# Nu_Preamp.net
KiCad netlist of a schematic drawn in EAGLE
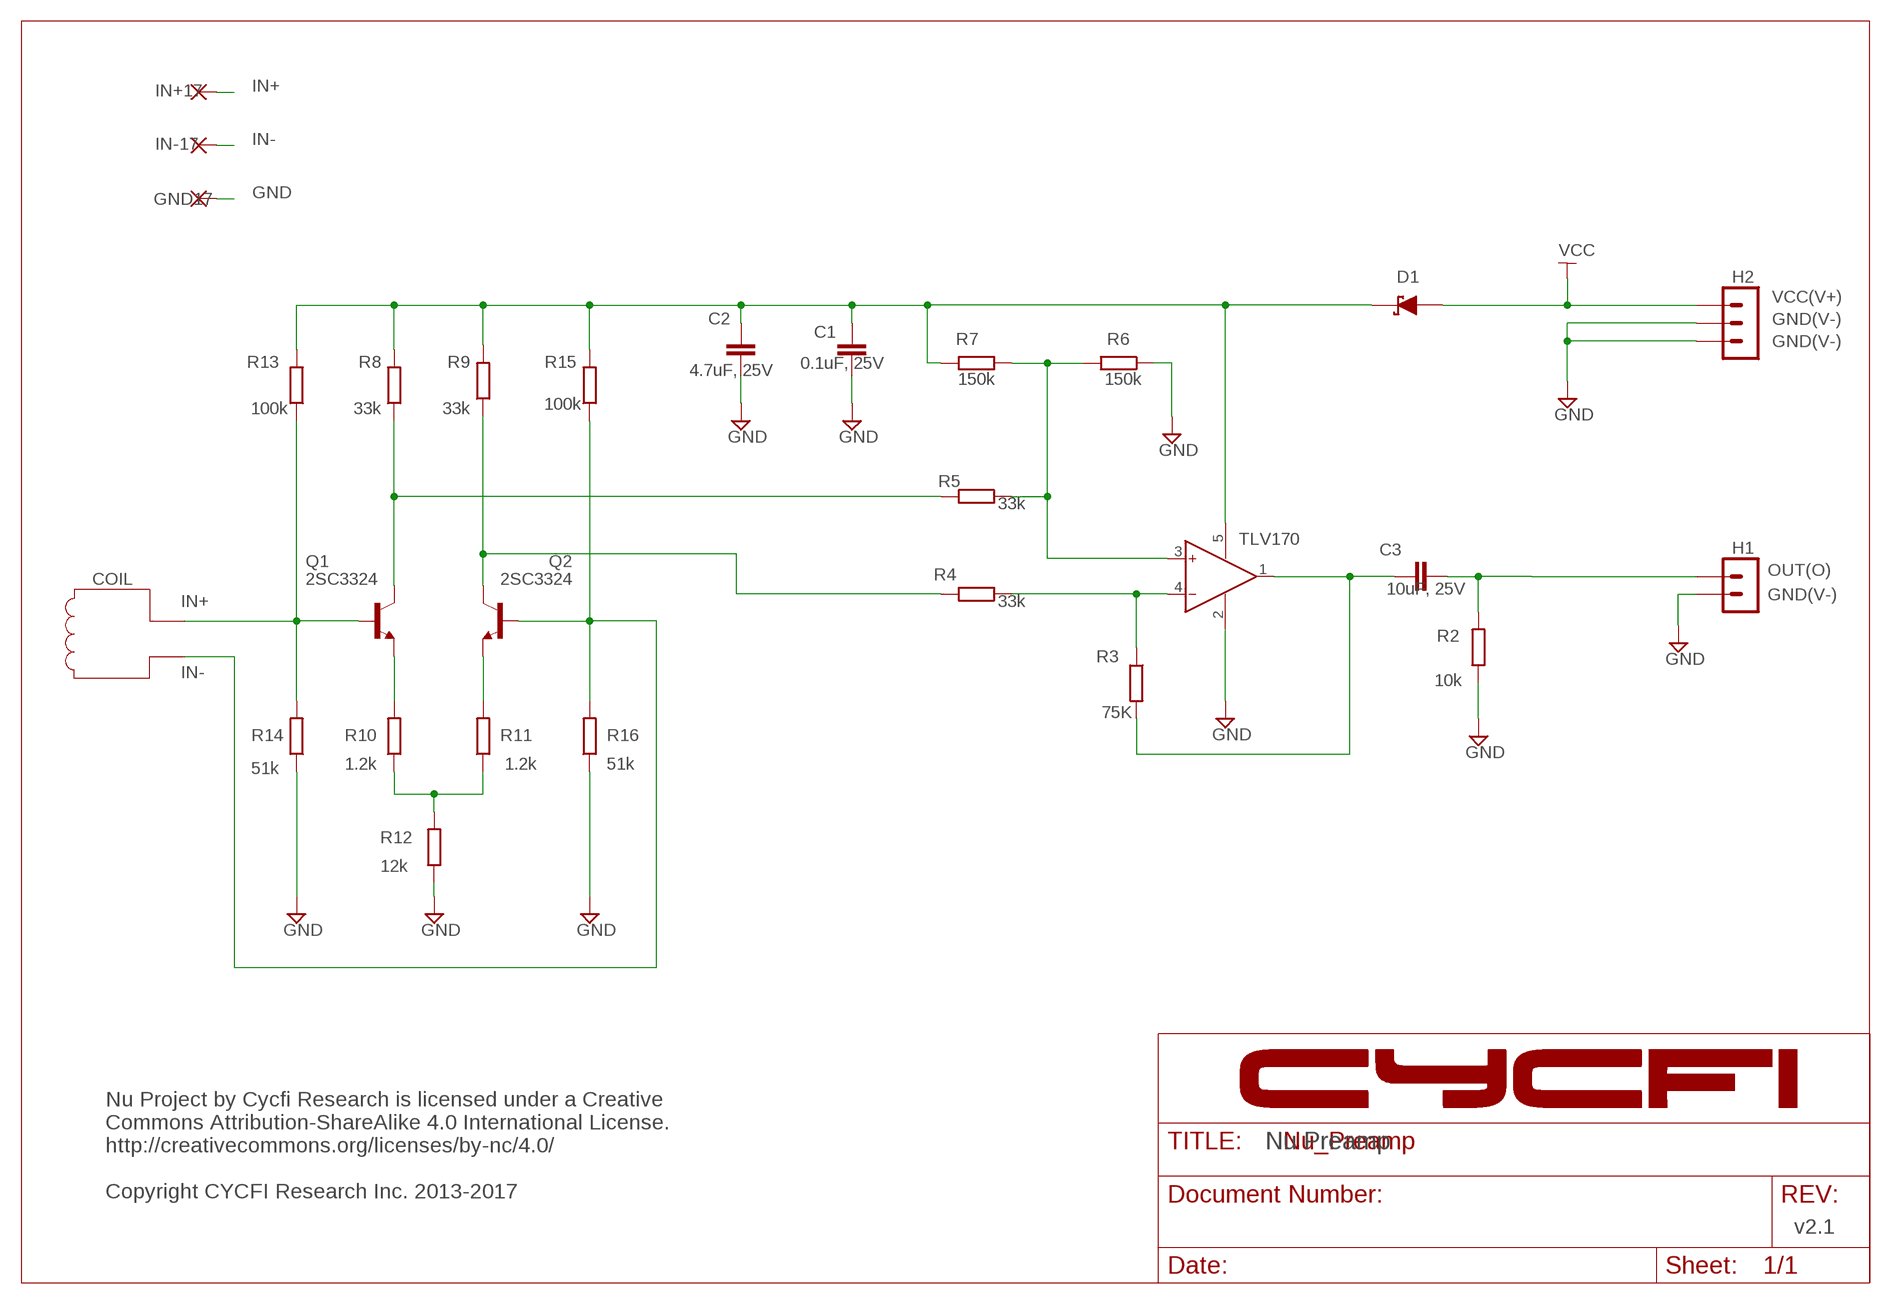
[diagram p0: schematic, sheet 1]

(export (version "E")
  (design (tool "Eeschema 10.0.6"))
  (components
    (comp (ref "C1")
      (value "0.1uF, 25V")
      (footprint "eagle-import:C0402")
      (libsource (lib "eagle-import") (part "C-EUC0402"))
    )
    (comp (ref "C2")
      (value "4.7uF, 25V")
      (footprint "eagle-import:C0603_NK")
      (libsource (lib "eagle-import") (part "C0603_NK"))
    )
    (comp (ref "C3")
      (value "10uF, 25V")
      (footprint "eagle-import:C0603_NK")
      (libsource (lib "eagle-import") (part "C0603_NK"))
    )
    (comp (ref "D1")
      (value "D-SCHOTKKY_SOD323")
      (footprint "eagle-import:SOD323")
      (libsource (lib "eagle-import") (part "D-SCHOTKKY_SOD323"))
    )
    (comp (ref "GND17")
      (value "SMD2")
      (footprint "eagle-import:SMD1,27-2,54")
      (libsource (lib "eagle-import") (part "SMD2"))
    )
    (comp (ref "H1")
      (value "2P-2MM-TH-MALE")
      (footprint "eagle-import:2P-2MM-TH")
      (libsource (lib "eagle-import") (part "2P-2MM-TH-MALE"))
    )
    (comp (ref "H2")
      (value "3P-2MM-TH-MALE")
      (footprint "eagle-import:3P-2MM-TH")
      (libsource (lib "eagle-import") (part "3P-2MM-TH-MALE"))
    )
    (comp (ref "IN+17")
      (value "SMD2")
      (footprint "eagle-import:SMD1,27-2,54")
      (libsource (lib "eagle-import") (part "SMD2"))
    )
    (comp (ref "IN-17")
      (value "SMD2")
      (footprint "eagle-import:SMD1,27-2,54")
      (libsource (lib "eagle-import") (part "SMD2"))
    )
    (comp (ref "Q1")
      (value "2SC3324")
      (footprint "eagle-import:SOT23")
      (libsource (lib "eagle-import") (part "2SC3324"))
    )
    (comp (ref "Q2")
      (value "2SC3324")
      (footprint "eagle-import:SOT23")
      (libsource (lib "eagle-import") (part "2SC3324"))
    )
    (comp (ref "R2")
      (value "10k")
      (footprint "eagle-import:R0402")
      (libsource (lib "eagle-import") (part "R-EU_R0402"))
    )
    (comp (ref "R3")
      (value "75K")
      (footprint "eagle-import:R0402")
      (libsource (lib "eagle-import") (part "R-EU_R0402"))
    )
    (comp (ref "R4")
      (value "33k")
      (footprint "eagle-import:R0402")
      (libsource (lib "eagle-import") (part "R-EU_R0402"))
    )
    (comp (ref "R5")
      (value "33k")
      (footprint "eagle-import:R0402")
      (libsource (lib "eagle-import") (part "R-EU_R0402"))
    )
    (comp (ref "R6")
      (value "150k")
      (footprint "eagle-import:R0402")
      (libsource (lib "eagle-import") (part "R-EU_R0402"))
    )
    (comp (ref "R7")
      (value "150k")
      (footprint "eagle-import:R0402")
      (libsource (lib "eagle-import") (part "R-EU_R0402"))
    )
    (comp (ref "R8")
      (value "33k")
      (footprint "eagle-import:R0402")
      (libsource (lib "eagle-import") (part "R-EU_R0402"))
    )
    (comp (ref "R9")
      (value "33k")
      (footprint "eagle-import:R0402")
      (libsource (lib "eagle-import") (part "R-EU_R0402"))
    )
    (comp (ref "R10")
      (value "1.2k")
      (footprint "eagle-import:R0402")
      (libsource (lib "eagle-import") (part "R-EU_R0402"))
    )
    (comp (ref "R11")
      (value "1.2k")
      (footprint "eagle-import:R0402")
      (libsource (lib "eagle-import") (part "R-EU_R0402"))
    )
    (comp (ref "R12")
      (value "12k")
      (footprint "eagle-import:R0402")
      (libsource (lib "eagle-import") (part "R-EU_R0402"))
    )
    (comp (ref "R13")
      (value "100k")
      (footprint "eagle-import:R0402")
      (libsource (lib "eagle-import") (part "R-EU_R0402"))
    )
    (comp (ref "R14")
      (value "51k")
      (footprint "eagle-import:R0402")
      (libsource (lib "eagle-import") (part "R-EU_R0402"))
    )
    (comp (ref "R15")
      (value "100k")
      (footprint "eagle-import:R0402")
      (libsource (lib "eagle-import") (part "R-EU_R0402"))
    )
    (comp (ref "R16")
      (value "51k")
      (footprint "eagle-import:R0402")
      (libsource (lib "eagle-import") (part "R-EU_R0402"))
    )
    (comp (ref "U1")
      (value "TLV170")
      (footprint "eagle-import:SOT23-5")
      (libsource (lib "eagle-import") (part "TLV170"))
    )
  )
  (nets
    (net (code "1") (name "/IN+") (class "Default")
      (node (ref "IN+17") (pin "1") (pinfunction "P_1") (pintype "passive"))
      (node (ref "Q1") (pin "1") (pinfunction "B_1") (pintype "passive"))
      (node (ref "R13") (pin "1") (pinfunction "1_1") (pintype "passive"))
      (node (ref "R14") (pin "2") (pinfunction "2_2") (pintype "passive"))
    )
    (net (code "2") (name "/IN-") (class "Default")
      (node (ref "IN-17") (pin "1") (pinfunction "P_1") (pintype "passive"))
      (node (ref "Q2") (pin "1") (pinfunction "B_1") (pintype "passive"))
      (node (ref "R15") (pin "1") (pinfunction "1_1") (pintype "passive"))
      (node (ref "R16") (pin "2") (pinfunction "2_2") (pintype "passive"))
    )
    (net (code "3") (name "GND") (class "Default")
      (node (ref "C1") (pin "2") (pinfunction "2_2") (pintype "passive"))
      (node (ref "C2") (pin "1") (pinfunction "1_1") (pintype "passive"))
      (node (ref "GND17") (pin "1") (pinfunction "P_1") (pintype "passive"))
      (node (ref "H1") (pin "P$2") (pinfunction "2_P$2") (pintype "passive"))
      (node (ref "H2") (pin "P$2") (pinfunction "2_P$2") (pintype "passive"))
      (node (ref "H2") (pin "P$3") (pinfunction "3_P$3") (pintype "passive"))
      (node (ref "R12") (pin "1") (pinfunction "1_1") (pintype "passive"))
      (node (ref "R14") (pin "1") (pinfunction "1_1") (pintype "passive"))
      (node (ref "R16") (pin "1") (pinfunction "1_1") (pintype "passive"))
      (node (ref "R2") (pin "1") (pinfunction "1_1") (pintype "passive"))
      (node (ref "R6") (pin "1") (pinfunction "1_1") (pintype "passive"))
      (node (ref "U1") (pin "2") (pinfunction "V-_2") (pintype "power_in"))
    )
    (net (code "4") (name "Net-(D1-A)") (class "Default")
      (node (ref "D1") (pin "1") (pinfunction "A_1") (pintype "passive"))
      (node (ref "H2") (pin "P$1") (pinfunction "1_P$1") (pintype "passive"))
    )
    (net (code "5") (name "Net-(D1-C)") (class "Default")
      (node (ref "C1") (pin "1") (pinfunction "1_1") (pintype "passive"))
      (node (ref "C2") (pin "2") (pinfunction "2_2") (pintype "passive"))
      (node (ref "D1") (pin "2") (pinfunction "C_2") (pintype "passive"))
      (node (ref "R13") (pin "2") (pinfunction "2_2") (pintype "passive"))
      (node (ref "R15") (pin "2") (pinfunction "2_2") (pintype "passive"))
      (node (ref "R7") (pin "2") (pinfunction "2_2") (pintype "passive"))
      (node (ref "R8") (pin "2") (pinfunction "2_2") (pintype "passive"))
      (node (ref "R9") (pin "2") (pinfunction "2_2") (pintype "passive"))
      (node (ref "U1") (pin "5") (pinfunction "V+_5") (pintype "power_in"))
    )
    (net (code "6") (name "Net-(H1-1)") (class "Default")
      (node (ref "C3") (pin "2") (pinfunction "2_2") (pintype "passive"))
      (node (ref "H1") (pin "P$1") (pinfunction "1_P$1") (pintype "passive"))
      (node (ref "R2") (pin "2") (pinfunction "2_2") (pintype "passive"))
    )
    (net (code "7") (name "Net-(Q1-C)") (class "Default")
      (node (ref "Q1") (pin "3") (pinfunction "C_3") (pintype "passive"))
      (node (ref "R5") (pin "2") (pinfunction "2_2") (pintype "passive"))
      (node (ref "R8") (pin "1") (pinfunction "1_1") (pintype "passive"))
    )
    (net (code "8") (name "Net-(Q1-E)") (class "Default")
      (node (ref "Q1") (pin "2") (pinfunction "E_2") (pintype "passive"))
      (node (ref "R10") (pin "2") (pinfunction "2_2") (pintype "passive"))
    )
    (net (code "9") (name "Net-(Q2-C)") (class "Default")
      (node (ref "Q2") (pin "3") (pinfunction "C_3") (pintype "passive"))
      (node (ref "R4") (pin "2") (pinfunction "2_2") (pintype "passive"))
      (node (ref "R9") (pin "1") (pinfunction "1_1") (pintype "passive"))
    )
    (net (code "10") (name "Net-(Q2-E)") (class "Default")
      (node (ref "Q2") (pin "2") (pinfunction "E_2") (pintype "passive"))
      (node (ref "R11") (pin "2") (pinfunction "2_2") (pintype "passive"))
    )
    (net (code "11") (name "Net-(R10-Pad1)") (class "Default")
      (node (ref "R10") (pin "1") (pinfunction "1_1") (pintype "passive"))
      (node (ref "R11") (pin "1") (pinfunction "1_1") (pintype "passive"))
      (node (ref "R12") (pin "2") (pinfunction "2_2") (pintype "passive"))
    )
    (net (code "12") (name "Net-(U1A-IN+)") (class "Default")
      (node (ref "R5") (pin "1") (pinfunction "1_1") (pintype "passive"))
      (node (ref "R6") (pin "2") (pinfunction "2_2") (pintype "passive"))
      (node (ref "R7") (pin "1") (pinfunction "1_1") (pintype "passive"))
      (node (ref "U1") (pin "3") (pinfunction "IN+_3") (pintype "input"))
    )
    (net (code "13") (name "Net-(U1A-IN-)") (class "Default")
      (node (ref "R3") (pin "1") (pinfunction "1_1") (pintype "passive"))
      (node (ref "R4") (pin "1") (pinfunction "1_1") (pintype "passive"))
      (node (ref "U1") (pin "4") (pinfunction "IN-_4") (pintype "input"))
    )
    (net (code "14") (name "Net-(U1A-OUT)") (class "Default")
      (node (ref "C3") (pin "1") (pinfunction "1_1") (pintype "passive"))
      (node (ref "R3") (pin "2") (pinfunction "2_2") (pintype "passive"))
      (node (ref "U1") (pin "1") (pinfunction "OUT_1") (pintype "output"))
    )
  )
)
